# sepic.net
KiCad netlist of a schematic drawn in Altium Designer
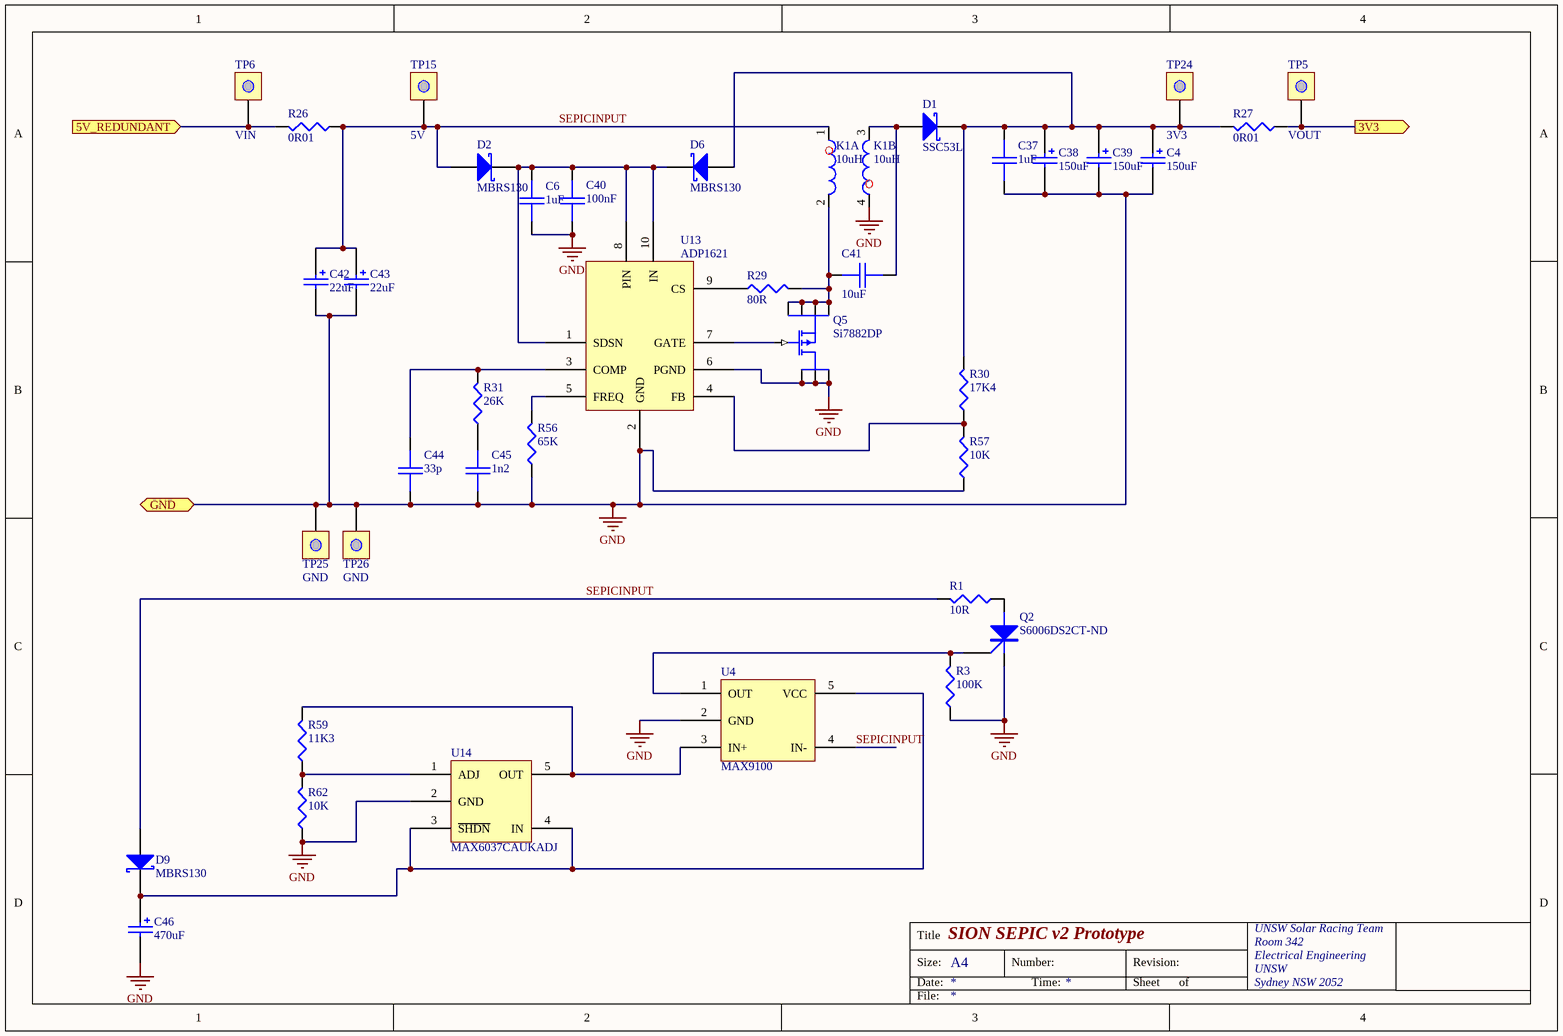
[diagram p0: sepic.SchDoc]

(export (version "E")
  (design (tool "Eeschema 10.0.6"))
  (components
    (comp (ref "C4")
      (value "150uF")
      (footprint "MCCT-CASED")
      (description "Polarized Capacitor (Surface Mount)")
      (fields (field (name "MANUFACTURER") "Generic Components") (field (name "PUBLISHER") "Altium Limited"))
      (libsource (lib "RCLDQ") (part "CAP POL3"))
    )
    (comp (ref "C6")
      (value "1uF")
      (footprint "0805")
      (description "Capacitor")
      (libsource (lib "RCLDQ") (part "CAP"))
    )
    (comp (ref "C37")
      (value "1uF")
      (footprint "0805")
      (description "Capacitor")
      (libsource (lib "RCLDQ") (part "CAP"))
    )
    (comp (ref "C38")
      (value "150uF")
      (footprint "MCCT-CASED")
      (description "Polarized Capacitor (Surface Mount)")
      (fields (field (name "MANUFACTURER") "Generic Components") (field (name "PUBLISHER") "Altium Limited"))
      (libsource (lib "RCLDQ") (part "CAP POL3"))
    )
    (comp (ref "C39")
      (value "150uF")
      (footprint "MCCT-CASED")
      (description "Polarized Capacitor (Surface Mount)")
      (fields (field (name "MANUFACTURER") "Generic Components") (field (name "PUBLISHER") "Altium Limited"))
      (libsource (lib "RCLDQ") (part "CAP POL3"))
    )
    (comp (ref "C40")
      (value "100nF")
      (footprint "0603")
      (description "Capacitor")
      (libsource (lib "RCLDQ") (part "CAP"))
    )
    (comp (ref "C41")
      (value "10uF")
      (footprint "0805")
      (description "grm21br61a106k")
      (libsource (lib "RCLDQ") (part "CAP"))
    )
    (comp (ref "C42")
      (value "22uF")
      (footprint "MCCT-CASEB")
      (description "Polarized Capacitor (Surface Mount)")
      (fields (field (name "MANUFACTURER") "Generic Components") (field (name "PUBLISHER") "Altium Limited"))
      (libsource (lib "RCLDQ") (part "CAP POL3"))
    )
    (comp (ref "C43")
      (value "22uF")
      (footprint "MCCT-CASEB")
      (description "Polarized Capacitor (Surface Mount)")
      (fields (field (name "MANUFACTURER") "Generic Components") (field (name "PUBLISHER") "Altium Limited"))
      (libsource (lib "RCLDQ") (part "CAP POL3"))
    )
    (comp (ref "C44")
      (value "33p")
      (footprint "0603")
      (description "Capacitor")
      (libsource (lib "RCLDQ") (part "CAP"))
    )
    (comp (ref "C45")
      (value "1n2")
      (footprint "0603")
      (description "Capacitor")
      (libsource (lib "RCLDQ") (part "CAP"))
    )
    (comp (ref "C46")
      (value "470uF")
      (footprint "MCCT-CASED")
      (description "Polarized Capacitor (Surface Mount)")
      (fields (field (name "MANUFACTURER") "Generic Components") (field (name "PUBLISHER") "Altium Limited"))
      (libsource (lib "RCLDQ") (part "CAP POL3"))
    )
    (comp (ref "D1")
      (value "SSC53L")
      (footprint "SMC")
      (description "Schottky Diode")
      (fields (field (name "MANUFACTURER") "Generic Components") (field (name "PUBLISHER") "Altium Limited"))
      (libsource (lib "RCLDQ") (part "D SCHOTTKY"))
    )
    (comp (ref "D2")
      (value "MBRS130")
      (footprint "SMB")
      (description "Schottky Diode")
      (fields (field (name "MANUFACTURER") "Generic Components") (field (name "PUBLISHER") "Altium Limited"))
      (libsource (lib "RCLDQ") (part "D SCHOTTKY"))
    )
    (comp (ref "D6")
      (value "MBRS130")
      (footprint "SMB")
      (description "Schottky Diode")
      (fields (field (name "MANUFACTURER") "Generic Components") (field (name "PUBLISHER") "Altium Limited"))
      (libsource (lib "RCLDQ") (part "D SCHOTTKY"))
    )
    (comp (ref "D9")
      (value "MBRS130")
      (footprint "SMB")
      (description "Schottky Diode")
      (fields (field (name "MANUFACTURER") "Generic Components") (field (name "PUBLISHER") "Altium Limited"))
      (libsource (lib "RCLDQ") (part "D SCHOTTKY"))
    )
    (comp (ref "K1")
      (value "10uH")
      (footprint "CTX2")
      (description "Coupled Power Inductor")
      (libsource (lib "sion") (part "CTX10-2-R"))
    )
    (comp (ref "Q2")
      (value "S6006DS2CT-ND")
      (footprint "DPAK_N-MOSFET")
      (description "Sensitive SCR")
      (libsource (lib "sion") (part "SCR"))
    )
    (comp (ref "Q5")
      (value "Si7882DP")
      (footprint "SO8")
      (description "Power N mosfet")
      (libsource (lib "sepic") (part "Si7882DP"))
    )
    (comp (ref "R1")
      (value "10R")
      (footprint "DIODE0.7")
      (description "Resistor")
      (libsource (lib "RCLDQ") (part "RES1"))
    )
    (comp (ref "R3")
      (value "100K")
      (footprint "1206")
      (description "Resistor")
      (libsource (lib "RCLDQ") (part "RES1"))
    )
    (comp (ref "R26")
      (value "0R01")
      (footprint "1206")
      (description "Resistor")
      (libsource (lib "RCLDQ") (part "RES1"))
    )
    (comp (ref "R27")
      (value "0R01")
      (footprint "1206")
      (description "Resistor")
      (libsource (lib "RCLDQ") (part "RES1"))
    )
    (comp (ref "R29")
      (value "80R")
      (footprint "0603")
      (description "Resistor")
      (libsource (lib "RCLDQ") (part "RES1"))
    )
    (comp (ref "R30")
      (value "17K4")
      (footprint "1206")
      (description "Resistor")
      (libsource (lib "RCLDQ") (part "RES1"))
    )
    (comp (ref "R31")
      (value "26K")
      (footprint "1206")
      (description "Resistor")
      (libsource (lib "RCLDQ") (part "RES1"))
    )
    (comp (ref "R56")
      (value "65K")
      (footprint "0603")
      (description "Resistor")
      (libsource (lib "RCLDQ") (part "RES1"))
    )
    (comp (ref "R57")
      (value "10K")
      (footprint "1206")
      (description "Resistor")
      (libsource (lib "RCLDQ") (part "RES1"))
    )
    (comp (ref "R59")
      (value "11K3")
      (footprint "1206")
      (description "Resistor")
      (libsource (lib "RCLDQ") (part "RES1"))
    )
    (comp (ref "R62")
      (value "10K")
      (footprint "1206")
      (description "Resistor")
      (libsource (lib "RCLDQ") (part "RES1"))
    )
    (comp (ref "TP5")
      (value "VOUT")
      (footprint "TESTPOINT")
      (description "TEST POINT")
      (libsource (lib "") (part "TEST_1"))
    )
    (comp (ref "TP6")
      (value "VIN")
      (footprint "TESTPOINT")
      (description "TEST POINT")
      (libsource (lib "") (part "TEST_1"))
    )
    (comp (ref "TP15")
      (value "5V")
      (footprint "TESTPOINT")
      (description "TEST POINT")
      (libsource (lib "") (part "TEST_1"))
    )
    (comp (ref "TP24")
      (value "3V3")
      (footprint "TESTPOINT")
      (description "TEST POINT")
      (libsource (lib "") (part "TEST_1"))
    )
    (comp (ref "TP25")
      (value "GND")
      (footprint "TESTPOINT")
      (description "TEST POINT")
      (libsource (lib "Miscellaneous") (part "TEST"))
    )
    (comp (ref "TP26")
      (value "GND")
      (footprint "TESTPOINT")
      (description "TEST POINT")
      (libsource (lib "Miscellaneous") (part "TEST"))
    )
    (comp (ref "U4")
      (value "MAX9100")
      (footprint "SOT23-5")
      (description "Micropower comparator")
      (libsource (lib "sion") (part "MAX9100EUK"))
    )
    (comp (ref "U13")
      (value "ADP1621")
      (footprint "MSOP10")
      (description "SEPIC / Boost Controller")
      (libsource (lib "sepic") (part "ADP1621"))
    )
    (comp (ref "U14")
      (value "MAX6037CAUKADJ")
      (footprint "SOT23-5")
      (description "Adjustable voltage reference")
      (libsource (lib "sion") (part "MAX6037CAUKADJ"))
    )
  )
  (nets
    (net (code "1") (name "/3V3") (class "Default")
      (node (ref "R27") (pin "1") (pinfunction "1_1") (pintype "passive"))
      (node (ref "TP5") (pin "0") (pinfunction "TP_0") (pintype "passive"))
    )
    (net (code "2") (name "/5V_REDUNDANT") (class "Default")
      (node (ref "R26") (pin "2") (pinfunction "2_2") (pintype "passive"))
      (node (ref "TP6") (pin "0") (pinfunction "TP_0") (pintype "passive"))
    )
    (net (code "3") (name "/SEPICINPUT") (class "Default")
      (node (ref "C42") (pin "1") (pinfunction "1_1") (pintype "passive"))
      (node (ref "C43") (pin "1") (pinfunction "1_1") (pintype "passive"))
      (node (ref "D2") (pin "A") (pinfunction "A_A") (pintype "passive"))
      (node (ref "D9") (pin "A") (pinfunction "A_A") (pintype "passive"))
      (node (ref "K1") (pin "1") (pinfunction "1_1") (pintype "passive"))
      (node (ref "R1") (pin "2") (pinfunction "2_2") (pintype "passive"))
      (node (ref "R26") (pin "1") (pinfunction "1_1") (pintype "passive"))
      (node (ref "TP15") (pin "0") (pinfunction "TP_0") (pintype "passive"))
      (node (ref "U4") (pin "4") (pinfunction "IN-_4") (pintype "passive"))
    )
    (net (code "4") (name "GND") (class "Default")
      (node (ref "C37") (pin "2") (pinfunction "2_2") (pintype "passive"))
      (node (ref "C38") (pin "2") (pinfunction "2_2") (pintype "passive"))
      (node (ref "C39") (pin "2") (pinfunction "2_2") (pintype "passive"))
      (node (ref "C4") (pin "2") (pinfunction "2_2") (pintype "passive"))
      (node (ref "C40") (pin "1") (pinfunction "1_1") (pintype "passive"))
      (node (ref "C42") (pin "2") (pinfunction "2_2") (pintype "passive"))
      (node (ref "C43") (pin "2") (pinfunction "2_2") (pintype "passive"))
      (node (ref "C44") (pin "2") (pinfunction "2_2") (pintype "passive"))
      (node (ref "C45") (pin "2") (pinfunction "2_2") (pintype "passive"))
      (node (ref "C46") (pin "2") (pinfunction "2_2") (pintype "passive"))
      (node (ref "C6") (pin "2") (pinfunction "2_2") (pintype "passive"))
      (node (ref "K1") (pin "4") (pinfunction "4_4") (pintype "passive"))
      (node (ref "Q2") (pin "1") (pinfunction "K_1") (pintype "passive"))
      (node (ref "Q5") (pin "1") (pinfunction "S_1") (pintype "bidirectional"))
      (node (ref "Q5") (pin "2") (pinfunction "S_2") (pintype "bidirectional"))
      (node (ref "Q5") (pin "3") (pinfunction "S_3") (pintype "bidirectional"))
      (node (ref "R3") (pin "1") (pinfunction "1_1") (pintype "passive"))
      (node (ref "R56") (pin "1") (pinfunction "1_1") (pintype "passive"))
      (node (ref "R57") (pin "1") (pinfunction "1_1") (pintype "passive"))
      (node (ref "R62") (pin "1") (pinfunction "1_1") (pintype "passive"))
      (node (ref "TP25") (pin "0") (pinfunction "TP_0") (pintype "passive"))
      (node (ref "TP26") (pin "0") (pinfunction "TP_0") (pintype "passive"))
      (node (ref "U13") (pin "2") (pinfunction "GND_2") (pintype "passive"))
      (node (ref "U13") (pin "6") (pinfunction "PGND_6") (pintype "passive"))
      (node (ref "U14") (pin "2") (pinfunction "GND_2") (pintype "passive"))
      (node (ref "U4") (pin "2") (pinfunction "GND_2") (pintype "passive"))
    )
    (net (code "5") (name "Net-(C41-Pad1)") (class "Default")
      (node (ref "C41") (pin "1") (pinfunction "1_1") (pintype "passive"))
      (node (ref "K1") (pin "2") (pinfunction "2_2") (pintype "passive"))
      (node (ref "Q5") (pin "5") (pinfunction "D_5") (pintype "bidirectional"))
      (node (ref "Q5") (pin "6") (pinfunction "D_6") (pintype "bidirectional"))
      (node (ref "Q5") (pin "7") (pinfunction "D_7") (pintype "bidirectional"))
      (node (ref "Q5") (pin "8") (pinfunction "D_8") (pintype "bidirectional"))
      (node (ref "R29") (pin "2") (pinfunction "2_2") (pintype "passive"))
    )
    (net (code "6") (name "Net-(C41-Pad2)") (class "Default")
      (node (ref "C41") (pin "2") (pinfunction "2_2") (pintype "passive"))
      (node (ref "D1") (pin "A") (pinfunction "A_A") (pintype "passive"))
      (node (ref "K1") (pin "3") (pinfunction "3_3") (pintype "passive"))
    )
    (net (code "7") (name "Net-(C45-Pad1)") (class "Default")
      (node (ref "C45") (pin "1") (pinfunction "1_1") (pintype "passive"))
      (node (ref "R31") (pin "1") (pinfunction "1_1") (pintype "passive"))
    )
    (net (code "8") (name "Net-(Q2-A)") (class "Default")
      (node (ref "Q2") (pin "2") (pinfunction "A_2") (pintype "passive"))
      (node (ref "R1") (pin "1") (pinfunction "1_1") (pintype "passive"))
    )
    (net (code "9") (name "Net-(Q2-G)") (class "Default")
      (node (ref "Q2") (pin "3") (pinfunction "G_3") (pintype "passive"))
      (node (ref "R3") (pin "2") (pinfunction "2_2") (pintype "passive"))
      (node (ref "U4") (pin "1") (pinfunction "OUT_1") (pintype "passive"))
    )
    (net (code "10") (name "Net-(Q5-G)") (class "Default")
      (node (ref "Q5") (pin "4") (pinfunction "G_4") (pintype "input"))
      (node (ref "U13") (pin "7") (pinfunction "GATE_7") (pintype "passive"))
    )
    (net (code "11") (name "Net-(TP24-TP)") (class "Default")
      (node (ref "C37") (pin "1") (pinfunction "1_1") (pintype "passive"))
      (node (ref "C38") (pin "1") (pinfunction "1_1") (pintype "passive"))
      (node (ref "C39") (pin "1") (pinfunction "1_1") (pintype "passive"))
      (node (ref "C4") (pin "1") (pinfunction "1_1") (pintype "passive"))
      (node (ref "D1") (pin "K") (pinfunction "K_K") (pintype "passive"))
      (node (ref "D6") (pin "A") (pinfunction "A_A") (pintype "passive"))
      (node (ref "R27") (pin "2") (pinfunction "2_2") (pintype "passive"))
      (node (ref "R30") (pin "2") (pinfunction "2_2") (pintype "passive"))
      (node (ref "TP24") (pin "0") (pinfunction "TP_0") (pintype "passive"))
    )
    (net (code "12") (name "Net-(U13-COMP)") (class "Default")
      (node (ref "C44") (pin "1") (pinfunction "1_1") (pintype "passive"))
      (node (ref "R31") (pin "2") (pinfunction "2_2") (pintype "passive"))
      (node (ref "U13") (pin "3") (pinfunction "COMP_3") (pintype "passive"))
    )
    (net (code "13") (name "Net-(U13-CS)") (class "Default")
      (node (ref "R29") (pin "1") (pinfunction "1_1") (pintype "passive"))
      (node (ref "U13") (pin "9") (pinfunction "CS_9") (pintype "passive"))
    )
    (net (code "14") (name "Net-(U13-FB)") (class "Default")
      (node (ref "R30") (pin "1") (pinfunction "1_1") (pintype "passive"))
      (node (ref "R57") (pin "2") (pinfunction "2_2") (pintype "passive"))
      (node (ref "U13") (pin "4") (pinfunction "FB_4") (pintype "passive"))
    )
    (net (code "15") (name "Net-(U13-FREQ)") (class "Default")
      (node (ref "R56") (pin "2") (pinfunction "2_2") (pintype "passive"))
      (node (ref "U13") (pin "5") (pinfunction "FREQ_5") (pintype "passive"))
    )
    (net (code "16") (name "Net-(U13-IN)") (class "Default")
      (node (ref "C40") (pin "2") (pinfunction "2_2") (pintype "passive"))
      (node (ref "C6") (pin "1") (pinfunction "1_1") (pintype "passive"))
      (node (ref "D2") (pin "K") (pinfunction "K_K") (pintype "passive"))
      (node (ref "D6") (pin "K") (pinfunction "K_K") (pintype "passive"))
      (node (ref "U13") (pin "1") (pinfunction "SDSN_1") (pintype "passive"))
      (node (ref "U13") (pin "10") (pinfunction "IN_10") (pintype "passive"))
      (node (ref "U13") (pin "8") (pinfunction "PIN_8") (pintype "passive"))
    )
    (net (code "17") (name "Net-(U14-ADJ)") (class "Default")
      (node (ref "R59") (pin "1") (pinfunction "1_1") (pintype "passive"))
      (node (ref "R62") (pin "2") (pinfunction "2_2") (pintype "passive"))
      (node (ref "U14") (pin "1") (pinfunction "ADJ_1") (pintype "passive"))
    )
    (net (code "18") (name "Net-(U14-IN)") (class "Default")
      (node (ref "C46") (pin "1") (pinfunction "1_1") (pintype "passive"))
      (node (ref "D9") (pin "K") (pinfunction "K_K") (pintype "passive"))
      (node (ref "U14") (pin "3") (pinfunction "~{SHDN}_3") (pintype "passive"))
      (node (ref "U14") (pin "4") (pinfunction "IN_4") (pintype "passive"))
      (node (ref "U4") (pin "5") (pinfunction "VCC_5") (pintype "passive"))
    )
    (net (code "19") (name "Net-(U14-OUT)") (class "Default")
      (node (ref "R59") (pin "2") (pinfunction "2_2") (pintype "passive"))
      (node (ref "U14") (pin "5") (pinfunction "OUT_5") (pintype "passive"))
      (node (ref "U4") (pin "3") (pinfunction "IN+_3") (pintype "passive"))
    )
  )
)
